# new_Led_strip_light_pcb.net
KiCad netlist of a schematic drawn in EasyEDA Pro
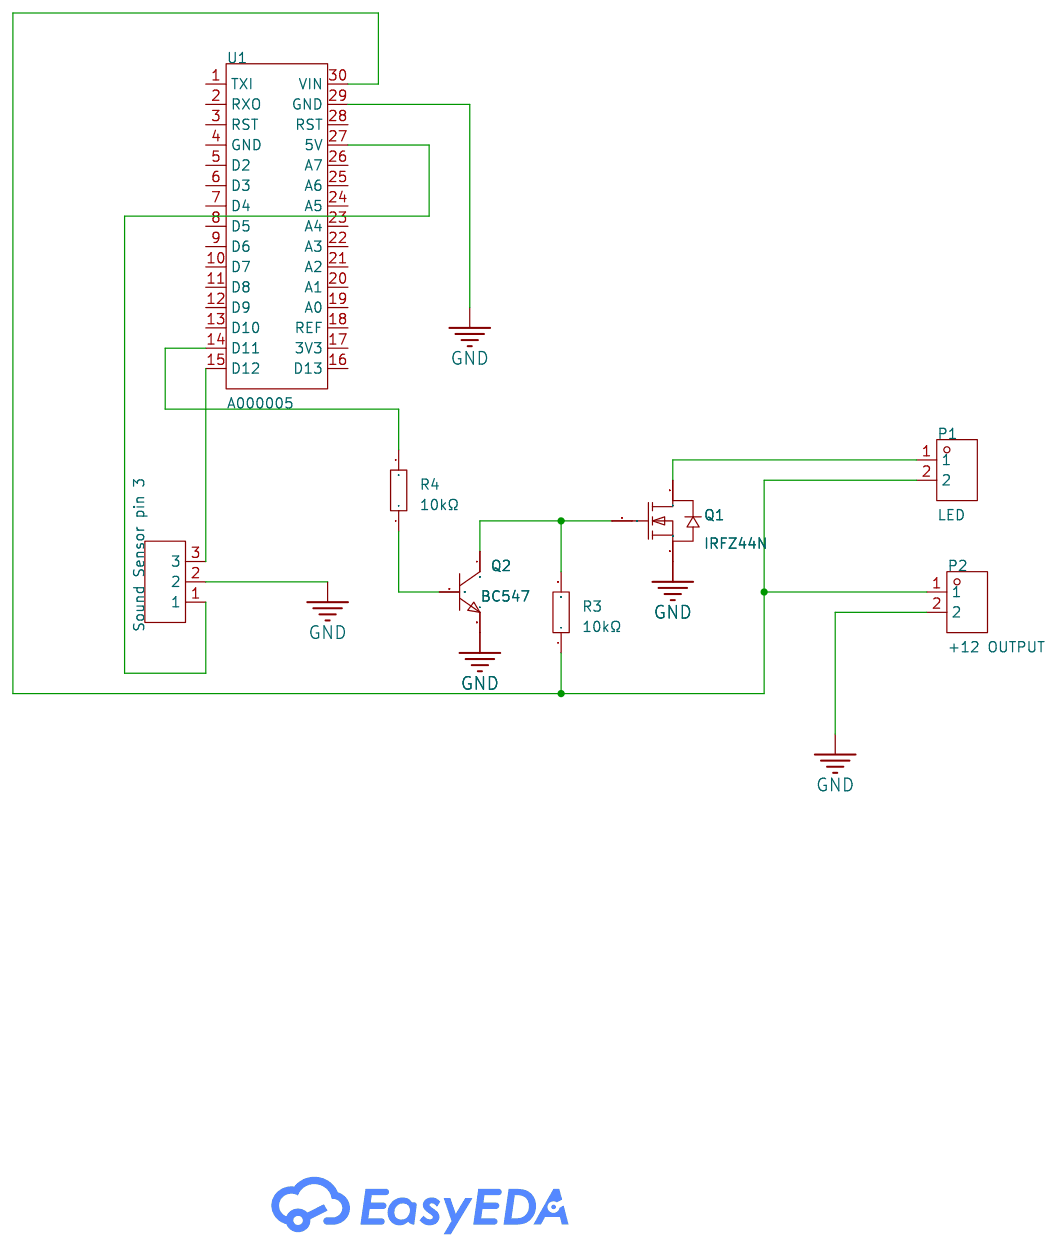
[diagram p0: schematic sheet]

(export (version "E")
  (design (tool "Eeschema 10.0.6"))
  (components
    (comp (ref "H1")
      (value "Sound Sensor pin 3")
      (footprint "easyedapro:HDR-TH_3P-P2.54-V-M-1")
      (fields
        (field (name "Manufacturer Part") "HX PH254-01-03-Z-L11.5 pcb pin header")
        (field (name "Manufacturer") "hanxia(韩下)")
      )
      (libsource (lib "easyedapro") (part "HX PH254-01-03-Z-L11.5 PCB PIN HEADER"))
    )
    (comp (ref "P1")
      (value "LED")
      (footprint "easyedapro:CONN-TH_2P-P5.08_DIBO_DB129S-5.08-2P-GN-S")
      (fields
        (field (name "Manufacturer Part") "DB129S-5.08-2P-GN-S")
        (field (name "Manufacturer") "DORABO(地博电气)")
      )
      (libsource (lib "easyedapro") (part "DB129S-5.08-2P-GN-S"))
    )
    (comp (ref "P2")
      (value "+12 OUTPUT")
      (footprint "easyedapro:CONN-TH_2P-P5.08_DIBO_DB129S-5.08-2P-GN-S")
      (fields
        (field (name "Manufacturer Part") "DB129S-5.08-2P-GN-S")
        (field (name "Manufacturer") "DORABO(地博电气)")
      )
      (libsource (lib "easyedapro") (part "DB129S-5.08-2P-GN-S"))
    )
    (comp (ref "Q1")
      (value "IRFZ44N")
      (footprint "easyedapro:TO-220-3_L9.9-W4.5-P2.54-L")
      (fields (field (name "Manufacturer") "minos(迈诺斯)"))
      (libsource (lib "easyedapro") (part "IRFZ44N"))
    )
    (comp (ref "Q2")
      (value "BC547")
      (footprint "easyedapro:TO-92-3_L4.9-W3.7-P1.27-L")
      (fields (field (name "Manufacturer") "CJ(江苏长电/长晶)"))
      (libsource (lib "easyedapro") (part "BC547_C47089404"))
    )
    (comp (ref "R3")
      (value "10kΩ")
      (footprint "easyedapro:R0402")
      (fields (field (name "Manufacturer Part") "RC0402FR-0710KL") (field (name "Manufacturer") "YAGEO(国巨)"))
      (libsource (lib "easyedapro") (part "RC0402FR-0710KL"))
    )
    (comp (ref "R4")
      (value "10kΩ")
      (footprint "easyedapro:R0402")
      (fields (field (name "Manufacturer Part") "RC0402FR-0710KL") (field (name "Manufacturer") "YAGEO(国巨)"))
      (libsource (lib "easyedapro") (part "RC0402FR-0710KL"))
    )
    (comp (ref "U1")
      (value "A000005")
      (footprint "easyedapro:COMM-TH_A000005")
      (fields (field (name "Manufacturer") "arduino"))
      (libsource (lib "easyedapro") (part "A000005"))
    )
  )
  (nets
    (net (code "1") (name "GND") (class "Default")
      (node (ref "H1") (pin "2") (pinfunction "2_2") (pintype "unspecified"))
      (node (ref "P2") (pin "2") (pinfunction "2_2") (pintype "unspecified"))
      (node (ref "Q1") (pin "3") (pinfunction "S_3") (pintype "unspecified"))
      (node (ref "Q2") (pin "3") (pinfunction "E_3") (pintype "input"))
      (node (ref "U1") (pin "29") (pinfunction "GND_29") (pintype "unspecified"))
    )
    (net (code "2") (name "Net-(Q1-D)") (class "Default")
      (node (ref "P1") (pin "1") (pinfunction "1_1") (pintype "unspecified"))
      (node (ref "Q1") (pin "2") (pinfunction "D_2") (pintype "unspecified"))
    )
    (net (code "3") (name "Net-(Q1-G)") (class "Default")
      (node (ref "Q1") (pin "1") (pinfunction "G_1") (pintype "unspecified"))
      (node (ref "Q2") (pin "1") (pinfunction "C_1") (pintype "input"))
      (node (ref "R3") (pin "2") (pinfunction "2_2") (pintype "input"))
    )
    (net (code "4") (name "Net-(Q2-B)") (class "Default")
      (node (ref "Q2") (pin "2") (pinfunction "B_2") (pintype "input"))
      (node (ref "R4") (pin "1") (pinfunction "1_1") (pintype "input"))
    )
    (net (code "5") (name "Net-(U1-5V)") (class "Default")
      (node (ref "H1") (pin "1") (pinfunction "1_1") (pintype "unspecified"))
      (node (ref "U1") (pin "27") (pinfunction "5V_27") (pintype "unspecified"))
    )
    (net (code "6") (name "Net-(U1-D11)") (class "Default")
      (node (ref "R4") (pin "2") (pinfunction "2_2") (pintype "input"))
      (node (ref "U1") (pin "14") (pinfunction "D11_14") (pintype "unspecified"))
    )
    (net (code "7") (name "Net-(U1-D12)") (class "Default")
      (node (ref "H1") (pin "3") (pinfunction "3_3") (pintype "unspecified"))
      (node (ref "U1") (pin "15") (pinfunction "D12_15") (pintype "unspecified"))
    )
    (net (code "8") (name "Net-(U1-VIN)") (class "Default")
      (node (ref "P1") (pin "2") (pinfunction "2_2") (pintype "unspecified"))
      (node (ref "P2") (pin "1") (pinfunction "1_1") (pintype "unspecified"))
      (node (ref "R3") (pin "1") (pinfunction "1_1") (pintype "input"))
      (node (ref "U1") (pin "30") (pinfunction "VIN_30") (pintype "unspecified"))
    )
    (net (code "9") (name "unconnected-(U1-3V3-Pad17)") (class "Default")
      (node (ref "U1") (pin "17") (pinfunction "3V3_17") (pintype "unspecified"))
    )
    (net (code "10") (name "unconnected-(U1-A0-Pad19)") (class "Default")
      (node (ref "U1") (pin "19") (pinfunction "A0_19") (pintype "unspecified"))
    )
    (net (code "11") (name "unconnected-(U1-A1-Pad20)") (class "Default")
      (node (ref "U1") (pin "20") (pinfunction "A1_20") (pintype "unspecified"))
    )
    (net (code "12") (name "unconnected-(U1-A2-Pad21)") (class "Default")
      (node (ref "U1") (pin "21") (pinfunction "A2_21") (pintype "unspecified"))
    )
    (net (code "13") (name "unconnected-(U1-A3-Pad22)") (class "Default")
      (node (ref "U1") (pin "22") (pinfunction "A3_22") (pintype "unspecified"))
    )
    (net (code "14") (name "unconnected-(U1-A4-Pad23)") (class "Default")
      (node (ref "U1") (pin "23") (pinfunction "A4_23") (pintype "unspecified"))
    )
    (net (code "15") (name "unconnected-(U1-A5-Pad24)") (class "Default")
      (node (ref "U1") (pin "24") (pinfunction "A5_24") (pintype "unspecified"))
    )
    (net (code "16") (name "unconnected-(U1-A6-Pad25)") (class "Default")
      (node (ref "U1") (pin "25") (pinfunction "A6_25") (pintype "unspecified"))
    )
    (net (code "17") (name "unconnected-(U1-A7-Pad26)") (class "Default")
      (node (ref "U1") (pin "26") (pinfunction "A7_26") (pintype "unspecified"))
    )
    (net (code "18") (name "unconnected-(U1-D2-Pad5)") (class "Default")
      (node (ref "U1") (pin "5") (pinfunction "D2_5") (pintype "unspecified"))
    )
    (net (code "19") (name "unconnected-(U1-D3-Pad6)") (class "Default")
      (node (ref "U1") (pin "6") (pinfunction "D3_6") (pintype "unspecified"))
    )
    (net (code "20") (name "unconnected-(U1-D4-Pad7)") (class "Default")
      (node (ref "U1") (pin "7") (pinfunction "D4_7") (pintype "unspecified"))
    )
    (net (code "21") (name "unconnected-(U1-D5-Pad8)") (class "Default")
      (node (ref "U1") (pin "8") (pinfunction "D5_8") (pintype "unspecified"))
    )
    (net (code "22") (name "unconnected-(U1-D6-Pad9)") (class "Default")
      (node (ref "U1") (pin "9") (pinfunction "D6_9") (pintype "unspecified"))
    )
    (net (code "23") (name "unconnected-(U1-D7-Pad10)") (class "Default")
      (node (ref "U1") (pin "10") (pinfunction "D7_10") (pintype "unspecified"))
    )
    (net (code "24") (name "unconnected-(U1-D8-Pad11)") (class "Default")
      (node (ref "U1") (pin "11") (pinfunction "D8_11") (pintype "unspecified"))
    )
    (net (code "25") (name "unconnected-(U1-D9-Pad12)") (class "Default")
      (node (ref "U1") (pin "12") (pinfunction "D9_12") (pintype "unspecified"))
    )
    (net (code "26") (name "unconnected-(U1-D10-Pad13)") (class "Default")
      (node (ref "U1") (pin "13") (pinfunction "D10_13") (pintype "unspecified"))
    )
    (net (code "27") (name "unconnected-(U1-D13-Pad16)") (class "Default")
      (node (ref "U1") (pin "16") (pinfunction "D13_16") (pintype "unspecified"))
    )
    (net (code "28") (name "unconnected-(U1-GND-Pad4)") (class "Default")
      (node (ref "U1") (pin "4") (pinfunction "GND_4") (pintype "unspecified"))
    )
    (net (code "29") (name "unconnected-(U1-REF-Pad18)") (class "Default")
      (node (ref "U1") (pin "18") (pinfunction "REF_18") (pintype "unspecified"))
    )
    (net (code "30") (name "unconnected-(U1-RST-Pad3)") (class "Default")
      (node (ref "U1") (pin "3") (pinfunction "RST_3") (pintype "unspecified"))
    )
    (net (code "31") (name "unconnected-(U1-RST-Pad28)") (class "Default")
      (node (ref "U1") (pin "28") (pinfunction "RST_28") (pintype "unspecified"))
    )
    (net (code "32") (name "unconnected-(U1-RXO-Pad2)") (class "Default")
      (node (ref "U1") (pin "2") (pinfunction "RXO_2") (pintype "unspecified"))
    )
    (net (code "33") (name "unconnected-(U1-TXI-Pad1)") (class "Default")
      (node (ref "U1") (pin "1") (pinfunction "TXI_1") (pintype "unspecified"))
    )
  )
)
